# PX4FMUv2_3_SCH4.net
KiCad netlist of a schematic drawn in Altium Designer
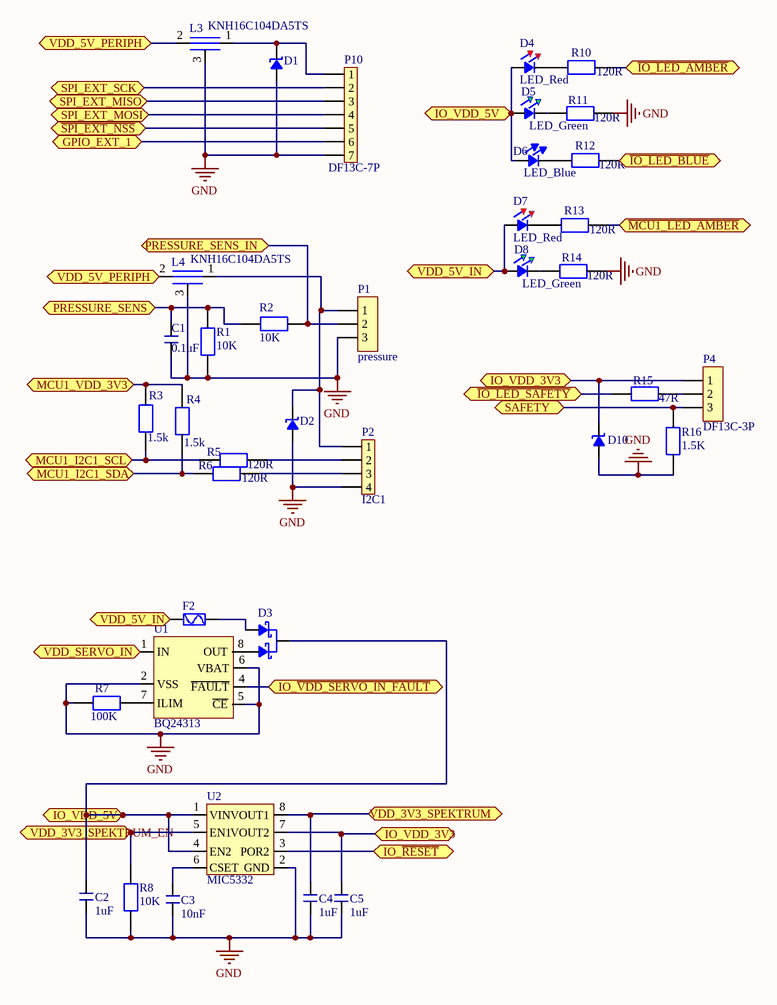
[diagram p0: PX4FMUv2.3_SCH4.SchDoc]

(export (version "E")
  (design (tool "Eeschema 10.0.6"))
  (components
    (comp (ref "C1") (value "0.1uF") (footprint "C 0402") (libsource (lib "px4_SCHLIB") (part "CAP_0402")))
    (comp (ref "C2") (value "1uF") (footprint "C 0603_L") (libsource (lib "px4_SCHLIB") (part "CAP_0603")))
    (comp (ref "C3") (value "10nF") (footprint "C 0402") (libsource (lib "px4_SCHLIB") (part "CAP_0402")))
    (comp (ref "C4") (value "1uF") (footprint "C 0603_L") (libsource (lib "px4_SCHLIB") (part "CAP_0603")))
    (comp (ref "C5") (value "1uF") (footprint "C 0603_L") (libsource (lib "px4_SCHLIB") (part "CAP_0603")))
    (comp (ref "D1")
      (value "PESD0402-140")
      (footprint "0402-TVS")
      (libsource (lib "px4_SCHLIB") (part "PESD0402-140"))
    )
    (comp (ref "D2")
      (value "PESD0402-140")
      (footprint "0402-TVS")
      (libsource (lib "px4_SCHLIB") (part "PESD0402-140"))
    )
    (comp (ref "D3")
      (value "PMEG2005CT")
      (footprint "SOT23")
      (libsource (lib "px4_SCHLIB") (part "PMEG2005CT"))
    )
    (comp (ref "D4")
      (value "LED_Red")
      (footprint "LED 0603R")
      (libsource (lib "px4_SCHLIB") (part "LED_Red"))
    )
    (comp (ref "D5")
      (value "LED_Green")
      (footprint "LED 0603G")
      (libsource (lib "px4_SCHLIB") (part "LED_Green"))
    )
    (comp (ref "D6")
      (value "LED_Blue")
      (footprint "LED 0603B")
      (libsource (lib "px4_SCHLIB") (part "LED_Blue"))
    )
    (comp (ref "D7")
      (value "LED_Red")
      (footprint "LED 0603R")
      (libsource (lib "px4_SCHLIB") (part "LED_Red"))
    )
    (comp (ref "D8")
      (value "LED_Green")
      (footprint "LED 0603G")
      (libsource (lib "px4_SCHLIB") (part "LED_Green"))
    )
    (comp (ref "D10")
      (value "PESD0402-140")
      (footprint "0402-TVS")
      (libsource (lib "px4_SCHLIB") (part "PESD0402-140"))
    )
    (comp (ref "F2")
      (value "0ZCA0035FF2G")
      (footprint "PTC-1206")
      (libsource (lib "px4_SCHLIB") (part "0ZCA0035FF2G"))
    )
    (comp (ref "L3")
      (value "KNH16C104DA5TS")
      (footprint "KYOCERA-KNH16-DA")
      (libsource (lib "px4_SCHLIB") (part "KNH16C104DA5TS"))
    )
    (comp (ref "L4")
      (value "KNH16C104DA5TS")
      (footprint "KYOCERA-KNH16-DA")
      (libsource (lib "px4_SCHLIB") (part "KNH16C104DA5TS"))
    )
    (comp (ref "P1")
      (value "pressure")
      (footprint "MX 1.25-LS-3P")
      (libsource (lib "px4_SCHLIB") (part "DF13C-3P"))
    )
    (comp (ref "P2")
      (value "I2C1")
      (footprint "MX 1.25-LS-4P")
      (libsource (lib "px4_SCHLIB") (part "DF13C-4P"))
    )
    (comp (ref "P4")
      (value "DF13C-3P")
      (footprint "MX 1.25-LS-3P")
      (libsource (lib "px4_SCHLIB") (part "DF13C-3P"))
    )
    (comp (ref "P10")
      (value "DF13C-7P")
      (footprint "MX 1.25-LS-7P")
      (libsource (lib "px4_SCHLIB") (part "DF13C-7P"))
    )
    (comp (ref "R1") (value "10K") (footprint "0402R") (libsource (lib "px4_SCHLIB") (part "Res_0402")))
    (comp (ref "R2") (value "10K") (footprint "0402R") (libsource (lib "px4_SCHLIB") (part "Res_0402")))
    (comp (ref "R3") (value "1.5k") (footprint "0402R") (libsource (lib "px4_SCHLIB") (part "Res_0402")))
    (comp (ref "R4") (value "1.5k") (footprint "0402R") (libsource (lib "px4_SCHLIB") (part "Res_0402")))
    (comp (ref "R5") (value "120R") (footprint "0402R") (libsource (lib "px4_SCHLIB") (part "Res_0402")))
    (comp (ref "R6") (value "120R") (footprint "0402R") (libsource (lib "px4_SCHLIB") (part "Res_0402")))
    (comp (ref "R7") (value "100K") (footprint "0402R") (libsource (lib "px4_SCHLIB") (part "Res_0402")))
    (comp (ref "R8") (value "10K") (footprint "0402R") (libsource (lib "px4_SCHLIB") (part "Res_0402")))
    (comp (ref "R10") (value "120R") (footprint "0402R") (libsource (lib "px4_SCHLIB") (part "Res_0402")))
    (comp (ref "R11") (value "120R") (footprint "0402R") (libsource (lib "px4_SCHLIB") (part "Res_0402")))
    (comp (ref "R12") (value "120R") (footprint "0402R") (libsource (lib "px4_SCHLIB") (part "Res_0402")))
    (comp (ref "R13") (value "120R") (footprint "0402R") (libsource (lib "px4_SCHLIB") (part "Res_0402")))
    (comp (ref "R14") (value "120R") (footprint "0402R") (libsource (lib "px4_SCHLIB") (part "Res_0402")))
    (comp (ref "R15") (value "47R") (footprint "0402R") (libsource (lib "px4_SCHLIB") (part "Res_0402")))
    (comp (ref "R16") (value "1.5K") (footprint "0402R") (libsource (lib "px4_SCHLIB") (part "Res_0402")))
    (comp (ref "U1") (value "BQ24313") (footprint "QFN8") (libsource (lib "px4_SCHLIB") (part "BQ24313")))
    (comp (ref "U2") (value "MIC5332") (footprint "QFN8") (libsource (lib "px4_SCHLIB") (part "MIC5332")))
  )
  (nets
    (net (code "1") (name "/GPIO_EXT_1") (class "Default")
      (node (ref "P10") (pin "6") (pinfunction "6_6") (pintype "passive"))
    )
    (net (code "2") (name "/IO_VDD_3V3") (class "Default")
      (node (ref "C5") (pin "1") (pinfunction "1_1") (pintype "passive"))
      (node (ref "D10") (pin "2") (pinfunction "2_2") (pintype "passive"))
      (node (ref "P4") (pin "1") (pinfunction "1_1") (pintype "passive"))
      (node (ref "U2") (pin "7") (pinfunction "VOUT2_7") (pintype "passive"))
    )
    (net (code "3") (name "/IO_VDD_5V") (class "Default")
      (node (ref "C2") (pin "1") (pinfunction "1_1") (pintype "passive"))
      (node (ref "D3") (pin "3") (pinfunction "3_3") (pintype "passive"))
      (node (ref "D4") (pin "3") (pinfunction "3_3") (pintype "passive"))
      (node (ref "D5") (pin "3") (pinfunction "3_3") (pintype "passive"))
      (node (ref "D6") (pin "3") (pinfunction "3_3") (pintype "passive"))
      (node (ref "U2") (pin "1") (pinfunction "VIN_1") (pintype "passive"))
      (node (ref "U2") (pin "4") (pinfunction "EN2_4") (pintype "passive"))
    )
    (net (code "4") (name "/IO_~{RESET}") (class "Default")
      (node (ref "U2") (pin "3") (pinfunction "POR2_3") (pintype "passive"))
    )
    (net (code "5") (name "/IO_~{VDD_SERVO_IN_FAULT}") (class "Default")
      (node (ref "U1") (pin "4") (pinfunction "~{FAULT}_4") (pintype "passive"))
    )
    (net (code "6") (name "/MCU1_I2C1_SCL") (class "Default")
      (node (ref "R3") (pin "1") (pinfunction "1_1") (pintype "passive"))
      (node (ref "R5") (pin "2") (pinfunction "2_2") (pintype "passive"))
    )
    (net (code "7") (name "/MCU1_I2C1_SDA") (class "Default")
      (node (ref "R4") (pin "1") (pinfunction "1_1") (pintype "passive"))
      (node (ref "R6") (pin "2") (pinfunction "2_2") (pintype "passive"))
    )
    (net (code "8") (name "/MCU1_VDD_3V3") (class "Default")
      (node (ref "R3") (pin "2") (pinfunction "2_2") (pintype "passive"))
      (node (ref "R4") (pin "2") (pinfunction "2_2") (pintype "passive"))
    )
    (net (code "9") (name "/PRESSURE_SENS") (class "Default")
      (node (ref "C1") (pin "1") (pinfunction "1_1") (pintype "passive"))
      (node (ref "R1") (pin "1") (pinfunction "1_1") (pintype "passive"))
      (node (ref "R2") (pin "1") (pinfunction "1_1") (pintype "passive"))
    )
    (net (code "10") (name "/PRESSURE_SENS_IN") (class "Default")
      (node (ref "P1") (pin "2") (pinfunction "2_2") (pintype "passive"))
      (node (ref "R2") (pin "2") (pinfunction "2_2") (pintype "passive"))
    )
    (net (code "11") (name "/SAFETY") (class "Default")
      (node (ref "P4") (pin "3") (pinfunction "3_3") (pintype "passive"))
      (node (ref "R16") (pin "1") (pinfunction "1_1") (pintype "passive"))
    )
    (net (code "12") (name "/SPI_EXT_MISO") (class "Default")
      (node (ref "P10") (pin "3") (pinfunction "3_3") (pintype "passive"))
    )
    (net (code "13") (name "/SPI_EXT_MOSI") (class "Default")
      (node (ref "P10") (pin "4") (pinfunction "4_4") (pintype "passive"))
    )
    (net (code "14") (name "/SPI_EXT_SCK") (class "Default")
      (node (ref "P10") (pin "2") (pinfunction "2_2") (pintype "passive"))
    )
    (net (code "15") (name "/VDD_3V3_SPEKTRUM") (class "Default")
      (node (ref "C4") (pin "1") (pinfunction "1_1") (pintype "passive"))
      (node (ref "U2") (pin "8") (pinfunction "VOUT1_8") (pintype "passive"))
    )
    (net (code "16") (name "/VDD_3V3_SPEKTRUM_EN") (class "Default")
      (node (ref "R8") (pin "1") (pinfunction "1_1") (pintype "passive"))
      (node (ref "U2") (pin "5") (pinfunction "EN1_5") (pintype "passive"))
    )
    (net (code "17") (name "/VDD_5V_IN") (class "Default")
      (node (ref "D7") (pin "3") (pinfunction "3_3") (pintype "passive"))
      (node (ref "D8") (pin "3") (pinfunction "3_3") (pintype "passive"))
      (node (ref "F2") (pin "4") (pinfunction "4_4") (pintype "passive"))
    )
    (net (code "18") (name "/VDD_5V_PERIPH") (class "Default")
      (node (ref "L3") (pin "2") (pinfunction "2_2") (pintype "passive"))
      (node (ref "L4") (pin "2") (pinfunction "2_2") (pintype "passive"))
    )
    (net (code "19") (name "/VDD_SERVO_IN") (class "Default")
      (node (ref "U1") (pin "1") (pinfunction "IN_1") (pintype "passive"))
    )
    (net (code "20") (name "/~{IO_LED_AMBER}") (class "Default")
      (node (ref "R10") (pin "2") (pinfunction "2_2") (pintype "passive"))
    )
    (net (code "21") (name "/~{IO_LED_BLUE}") (class "Default")
      (node (ref "R12") (pin "1") (pinfunction "1_1") (pintype "passive"))
    )
    (net (code "22") (name "/~{IO_LED_SAFETY}") (class "Default")
      (node (ref "R15") (pin "2") (pinfunction "2_2") (pintype "passive"))
    )
    (net (code "23") (name "/~{MCU1_LED_AMBER}") (class "Default")
      (node (ref "R13") (pin "2") (pinfunction "2_2") (pintype "passive"))
    )
    (net (code "24") (name "/~{SPI_EXT_NSS}") (class "Default")
      (node (ref "P10") (pin "5") (pinfunction "5_5") (pintype "passive"))
    )
    (net (code "25") (name "GND") (class "Default")
      (node (ref "C1") (pin "2") (pinfunction "2_2") (pintype "passive"))
      (node (ref "C2") (pin "2") (pinfunction "2_2") (pintype "passive"))
      (node (ref "C3") (pin "2") (pinfunction "2_2") (pintype "passive"))
      (node (ref "C4") (pin "2") (pinfunction "2_2") (pintype "passive"))
      (node (ref "C5") (pin "2") (pinfunction "2_2") (pintype "passive"))
      (node (ref "D1") (pin "1") (pinfunction "1_1") (pintype "passive"))
      (node (ref "D10") (pin "1") (pinfunction "1_1") (pintype "passive"))
      (node (ref "D2") (pin "1") (pinfunction "1_1") (pintype "passive"))
      (node (ref "L3") (pin "3") (pinfunction "3_3") (pintype "passive"))
      (node (ref "L4") (pin "3") (pinfunction "3_3") (pintype "passive"))
      (node (ref "P1") (pin "3") (pinfunction "3_3") (pintype "passive"))
      (node (ref "P10") (pin "7") (pinfunction "7_7") (pintype "passive"))
      (node (ref "P2") (pin "4") (pinfunction "4_4") (pintype "passive"))
      (node (ref "R1") (pin "2") (pinfunction "2_2") (pintype "passive"))
      (node (ref "R11") (pin "1") (pinfunction "1_1") (pintype "passive"))
      (node (ref "R14") (pin "1") (pinfunction "1_1") (pintype "passive"))
      (node (ref "R16") (pin "2") (pinfunction "2_2") (pintype "passive"))
      (node (ref "R7") (pin "2") (pinfunction "2_2") (pintype "passive"))
      (node (ref "R8") (pin "2") (pinfunction "2_2") (pintype "passive"))
      (node (ref "U1") (pin "2") (pinfunction "VSS_2") (pintype "passive"))
      (node (ref "U1") (pin "5") (pinfunction "~{CE}_5") (pintype "passive"))
      (node (ref "U1") (pin "6") (pinfunction "VBAT_6") (pintype "passive"))
      (node (ref "U2") (pin "2") (pinfunction "GND_2") (pintype "passive"))
    )
    (net (code "26") (name "Net-(D1-Pad2)") (class "Default")
      (node (ref "D1") (pin "2") (pinfunction "2_2") (pintype "passive"))
      (node (ref "L3") (pin "1") (pinfunction "1_1") (pintype "passive"))
      (node (ref "P10") (pin "1") (pinfunction "1_1") (pintype "passive"))
    )
    (net (code "27") (name "Net-(D2-Pad2)") (class "Default")
      (node (ref "D2") (pin "2") (pinfunction "2_2") (pintype "passive"))
      (node (ref "L4") (pin "1") (pinfunction "1_1") (pintype "passive"))
      (node (ref "P1") (pin "1") (pinfunction "1_1") (pintype "passive"))
      (node (ref "P2") (pin "1") (pinfunction "1_1") (pintype "passive"))
    )
    (net (code "28") (name "Net-(D3-Pad1)") (class "Default")
      (node (ref "D3") (pin "1") (pinfunction "1_1") (pintype "passive"))
      (node (ref "F2") (pin "5") (pinfunction "5_5") (pintype "passive"))
    )
    (net (code "29") (name "Net-(D4-Pad4)") (class "Default")
      (node (ref "D4") (pin "4") (pinfunction "4_4") (pintype "passive"))
      (node (ref "R10") (pin "1") (pinfunction "1_1") (pintype "passive"))
    )
    (net (code "30") (name "Net-(D5-Pad4)") (class "Default")
      (node (ref "D5") (pin "4") (pinfunction "4_4") (pintype "passive"))
      (node (ref "R11") (pin "2") (pinfunction "2_2") (pintype "passive"))
    )
    (net (code "31") (name "Net-(D6-Pad4)") (class "Default")
      (node (ref "D6") (pin "4") (pinfunction "4_4") (pintype "passive"))
      (node (ref "R12") (pin "2") (pinfunction "2_2") (pintype "passive"))
    )
    (net (code "32") (name "Net-(D7-Pad4)") (class "Default")
      (node (ref "D7") (pin "4") (pinfunction "4_4") (pintype "passive"))
      (node (ref "R13") (pin "1") (pinfunction "1_1") (pintype "passive"))
    )
    (net (code "33") (name "Net-(D8-Pad4)") (class "Default")
      (node (ref "D8") (pin "4") (pinfunction "4_4") (pintype "passive"))
      (node (ref "R14") (pin "2") (pinfunction "2_2") (pintype "passive"))
    )
    (net (code "34") (name "Net-(P2-Pad2)") (class "Default")
      (node (ref "P2") (pin "2") (pinfunction "2_2") (pintype "passive"))
      (node (ref "R5") (pin "1") (pinfunction "1_1") (pintype "passive"))
    )
    (net (code "35") (name "Net-(P2-Pad3)") (class "Default")
      (node (ref "P2") (pin "3") (pinfunction "3_3") (pintype "passive"))
      (node (ref "R6") (pin "1") (pinfunction "1_1") (pintype "passive"))
    )
    (net (code "36") (name "Net-(P4-Pad2)") (class "Default")
      (node (ref "P4") (pin "2") (pinfunction "2_2") (pintype "passive"))
      (node (ref "R15") (pin "1") (pinfunction "1_1") (pintype "passive"))
    )
    (net (code "37") (name "Net-(U1-ILIM)") (class "Default")
      (node (ref "R7") (pin "1") (pinfunction "1_1") (pintype "passive"))
      (node (ref "U1") (pin "7") (pinfunction "ILIM_7") (pintype "passive"))
    )
    (net (code "38") (name "Net-(U1-OUT)") (class "Default")
      (node (ref "D3") (pin "2") (pinfunction "2_2") (pintype "passive"))
      (node (ref "U1") (pin "8") (pinfunction "OUT_8") (pintype "passive"))
    )
    (net (code "39") (name "Net-(U2-CSET)") (class "Default")
      (node (ref "C3") (pin "1") (pinfunction "1_1") (pintype "passive"))
      (node (ref "U2") (pin "6") (pinfunction "CSET_6") (pintype "passive"))
    )
  )
)
